# main-board.net
KiCad netlist of a schematic drawn in EAGLE
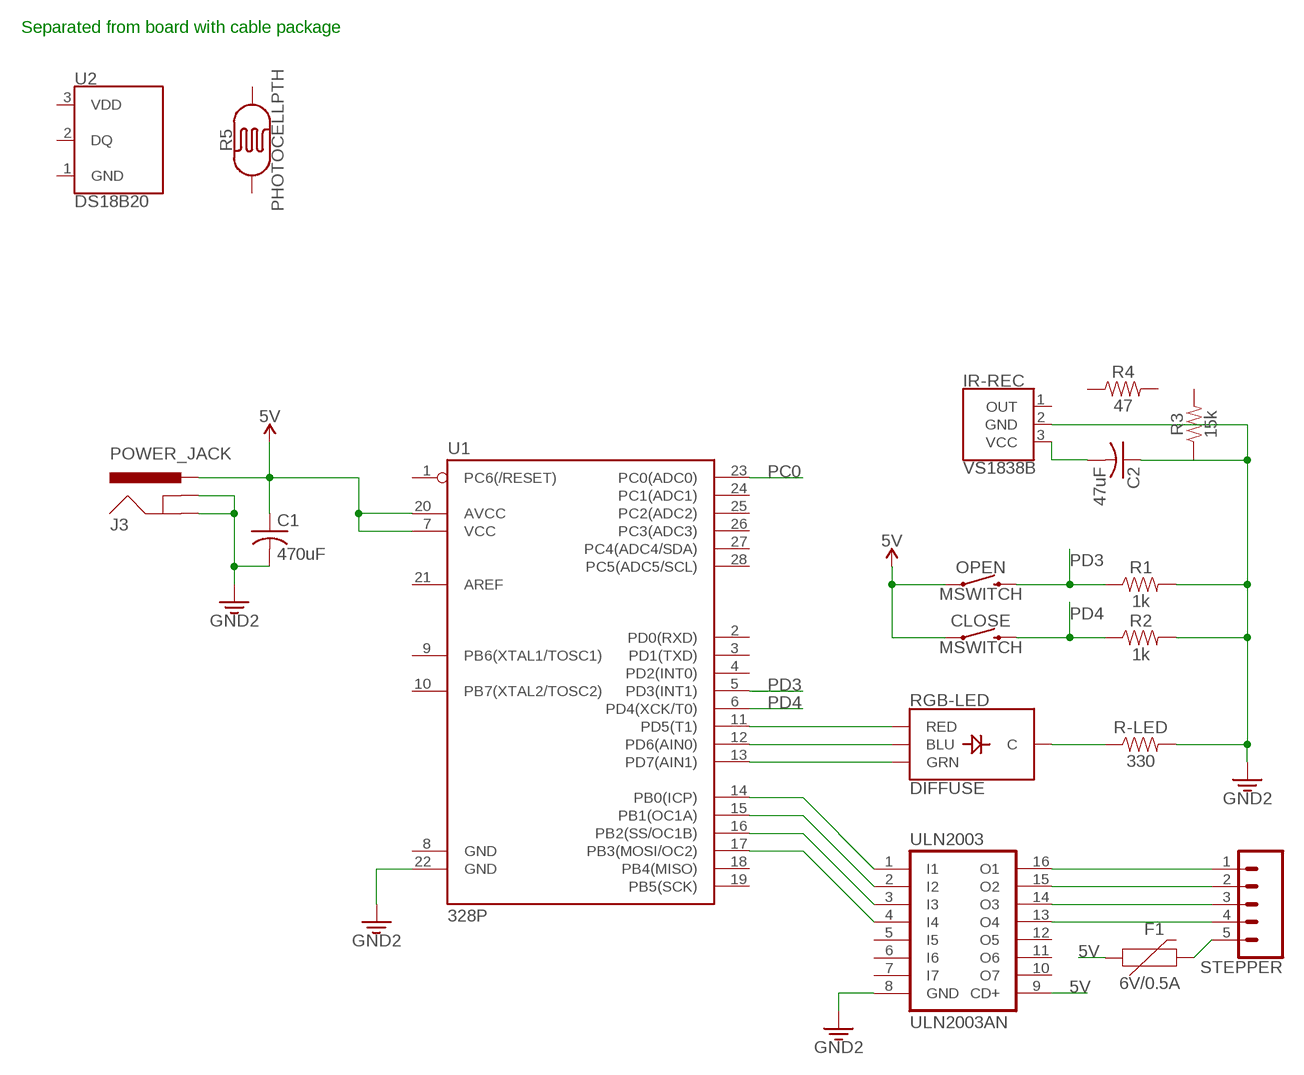
[diagram p0: schematic, sheet 1]

(export (version "E")
  (design (tool "Eeschema 10.0.6"))
  (components
    (comp (ref "C1")
      (value "470uF")
      (footprint "eagle-import:C025-050X050")
      (libsource (lib "eagle-import") (part "C-US025-050X050"))
    )
    (comp (ref "C2")
      (value "47uF")
      (footprint "eagle-import:C025-050X050")
      (libsource (lib "eagle-import") (part "C-US025-050X050"))
    )
    (comp (ref "CLOSE")
      (value "MSWITCH")
      (footprint "eagle-import:TACTILE_SWITCH_PTH_6.0MM")
      (libsource (lib "eagle-import") (part "MOMENTARY-SWITCH-SPST-PTH-6.0MM"))
    )
    (comp (ref "F1")
      (value "6V/0.5A")
      (footprint "eagle-import:1206")
      (fields (field (name "SPICEPREFIX") "F"))
      (libsource (lib "eagle-import") (part "PPTC_HALF-AMP"))
    )
    (comp (ref "IR-REC")
      (value "VS1838B")
      (footprint "eagle-import:BRM-2508_VERT")
      (libsource (lib "eagle-import") (part "BRM-2A18VERT"))
    )
    (comp (ref "J3")
      (value "POWER_JACK")
      (footprint "eagle-import:POWER_JACK_PTH")
      (libsource (lib "eagle-import") (part "POWER_JACK"))
    )
    (comp (ref "OPEN")
      (value "MSWITCH")
      (footprint "eagle-import:TACTILE_SWITCH_PTH_6.0MM")
      (libsource (lib "eagle-import") (part "MOMENTARY-SWITCH-SPST-PTH-6.0MM"))
    )
    (comp (ref "R-LED")
      (value "330")
      (footprint "eagle-import:AXIAL-0.3")
      (libsource (lib "eagle-import") (part "RESISTORAXIAL-0.3"))
    )
    (comp (ref "R1")
      (value "1k")
      (footprint "eagle-import:AXIAL-0.3")
      (libsource (lib "eagle-import") (part "1KOHM-HORIZ-1/4W-1%"))
    )
    (comp (ref "R2")
      (value "1k")
      (footprint "eagle-import:AXIAL-0.3")
      (libsource (lib "eagle-import") (part "1KOHM-HORIZ-1/4W-1%"))
    )
    (comp (ref "R3")
      (value "15k")
      (footprint "eagle-import:AXIAL-0.3")
      (libsource (lib "eagle-import") (part "RESISTORAXIAL-0.3"))
    )
    (comp (ref "R4")
      (value "47")
      (footprint "eagle-import:AXIAL-0.3")
      (libsource (lib "eagle-import") (part "RESISTORAXIAL-0.3"))
    )
    (comp (ref "R5")
      (value "PHOTOCELLPTH")
      (footprint "eagle-import:PHOTOCELL")
      (libsource (lib "eagle-import") (part "PHOTOCELLPTH"))
    )
    (comp (ref "RGB-LED")
      (value "DIFFUSE")
      (footprint "eagle-import:LED-RGB-THRU")
      (libsource (lib "eagle-import") (part "LED-RGB-CCDIFFUSE"))
    )
    (comp (ref "STEPPER")
      (value "CONN_05JST-VERT")
      (footprint "eagle-import:JST-5-PTH-VERT")
      (libsource (lib "eagle-import") (part "CONN_05JST-VERT"))
    )
    (comp (ref "U1")
      (value "328P")
      (footprint "eagle-import:DIP28")
      (libsource (lib "eagle-import") (part "ATMEGA328P_PDIP"))
    )
    (comp (ref "U2")
      (value "DS18B20")
      (footprint "eagle-import:TO-92-AMMO")
      (libsource (lib "eagle-import") (part "DS18B20"))
    )
    (comp (ref "ULN2003")
      (value "ULN2003AN")
      (footprint "eagle-import:DIL16")
      (libsource (lib "eagle-import") (part "ULN2003AN"))
    )
  )
  (nets
    (net (code "1") (name "/GND") (class "Default")
      (node (ref "U2") (pin "1") (pinfunction "GND_1") (pintype "power_in"))
    )
    (net (code "2") (name "/PC0") (class "Default")
      (node (ref "U1") (pin "23") (pinfunction "PC0(ADC0)_23") (pintype "bidirectional"))
    )
    (net (code "3") (name "/PD3") (class "Default")
      (node (ref "OPEN") (pin "3") (pinfunction "2_3") (pintype "passive"))
      (node (ref "R1") (pin "P$1") (pinfunction "1_P$1") (pintype "passive"))
      (node (ref "U1") (pin "5") (pinfunction "PD3(INT1)_5") (pintype "bidirectional"))
    )
    (net (code "4") (name "/PD4") (class "Default")
      (node (ref "CLOSE") (pin "3") (pinfunction "2_3") (pintype "passive"))
      (node (ref "R2") (pin "P$1") (pinfunction "1_P$1") (pintype "passive"))
      (node (ref "U1") (pin "6") (pinfunction "PD4(XCK/T0)_6") (pintype "bidirectional"))
    )
    (net (code "5") (name "/VDD") (class "Default")
      (node (ref "U2") (pin "3") (pinfunction "VDD_3") (pintype "power_in"))
    )
    (net (code "6") (name "5V") (class "Default")
      (node (ref "C1") (pin "1") (pinfunction "1_1") (pintype "passive"))
      (node (ref "CLOSE") (pin "1") (pinfunction "1_1") (pintype "passive"))
      (node (ref "F1") (pin "1") (pinfunction "1_1") (pintype "bidirectional"))
      (node (ref "J3") (pin "PWR") (pinfunction "PWR_PWR") (pintype "bidirectional"))
      (node (ref "OPEN") (pin "1") (pinfunction "1_1") (pintype "passive"))
      (node (ref "U1") (pin "20") (pinfunction "AVCC_20") (pintype "bidirectional"))
      (node (ref "U1") (pin "7") (pinfunction "VCC_7") (pintype "bidirectional"))
      (node (ref "ULN2003") (pin "9") (pinfunction "CD+_9") (pintype "passive"))
    )
    (net (code "7") (name "GND2") (class "Default")
      (node (ref "C1") (pin "2") (pinfunction "2_2") (pintype "passive"))
      (node (ref "C2") (pin "1") (pinfunction "1_1") (pintype "passive"))
      (node (ref "IR-REC") (pin "2") (pinfunction "GND_2") (pintype "bidirectional"))
      (node (ref "J3") (pin "GND") (pinfunction "GND_GND") (pintype "bidirectional"))
      (node (ref "J3") (pin "GNDBREAK") (pinfunction "GNDBREAK_GNDBREAK") (pintype "bidirectional"))
      (node (ref "R-LED") (pin "P$2") (pinfunction "2_P$2") (pintype "passive"))
      (node (ref "R1") (pin "P$2") (pinfunction "2_P$2") (pintype "passive"))
      (node (ref "R2") (pin "P$2") (pinfunction "2_P$2") (pintype "passive"))
      (node (ref "U1") (pin "22") (pinfunction "GND_22") (pintype "bidirectional"))
      (node (ref "ULN2003") (pin "8") (pinfunction "GND_8") (pintype "power_in"))
    )
    (net (code "8") (name "Net-(F1-Pad2)") (class "Default")
      (node (ref "F1") (pin "2") (pinfunction "2_2") (pintype "bidirectional"))
      (node (ref "STEPPER") (pin "5") (pinfunction "5_5") (pintype "passive"))
    )
    (net (code "9") (name "Net-(IR-REC-VCC)") (class "Default")
      (node (ref "C2") (pin "2") (pinfunction "2_2") (pintype "passive"))
      (node (ref "IR-REC") (pin "3") (pinfunction "VCC_3") (pintype "bidirectional"))
    )
    (net (code "10") (name "Net-(R-LED-1)") (class "Default")
      (node (ref "R-LED") (pin "P$1") (pinfunction "1_P$1") (pintype "passive"))
      (node (ref "RGB-LED") (pin "2") (pinfunction "C_2") (pintype "bidirectional"))
    )
    (net (code "11") (name "Net-(RGB-LED-BLU)") (class "Default")
      (node (ref "RGB-LED") (pin "4") (pinfunction "BLU_4") (pintype "bidirectional"))
      (node (ref "U1") (pin "12") (pinfunction "PD6(AIN0)_12") (pintype "bidirectional"))
    )
    (net (code "12") (name "Net-(RGB-LED-GRN)") (class "Default")
      (node (ref "RGB-LED") (pin "3") (pinfunction "GRN_3") (pintype "bidirectional"))
      (node (ref "U1") (pin "13") (pinfunction "PD7(AIN1)_13") (pintype "bidirectional"))
    )
    (net (code "13") (name "Net-(RGB-LED-RED)") (class "Default")
      (node (ref "RGB-LED") (pin "1") (pinfunction "RED_1") (pintype "bidirectional"))
      (node (ref "U1") (pin "11") (pinfunction "PD5(T1)_11") (pintype "bidirectional"))
    )
    (net (code "14") (name "Net-(U1-PB0(ICP))") (class "Default")
      (node (ref "U1") (pin "14") (pinfunction "PB0(ICP)_14") (pintype "bidirectional"))
      (node (ref "ULN2003") (pin "1") (pinfunction "I1_1") (pintype "input"))
    )
    (net (code "15") (name "Net-(U1-PB1(OC1A))") (class "Default")
      (node (ref "U1") (pin "15") (pinfunction "PB1(OC1A)_15") (pintype "bidirectional"))
      (node (ref "ULN2003") (pin "2") (pinfunction "I2_2") (pintype "input"))
    )
    (net (code "16") (name "Net-(U1-PB2(SS{slash}OC1B))") (class "Default")
      (node (ref "U1") (pin "16") (pinfunction "PB2(SS/OC1B)_16") (pintype "bidirectional"))
      (node (ref "ULN2003") (pin "3") (pinfunction "I3_3") (pintype "input"))
    )
    (net (code "17") (name "Net-(U1-PB3(MOSI{slash}OC2))") (class "Default")
      (node (ref "U1") (pin "17") (pinfunction "PB3(MOSI/OC2)_17") (pintype "bidirectional"))
      (node (ref "ULN2003") (pin "4") (pinfunction "I4_4") (pintype "input"))
    )
    (net (code "18") (name "Net-(ULN2003-O1)") (class "Default")
      (node (ref "STEPPER") (pin "1") (pinfunction "1_1") (pintype "passive"))
      (node (ref "ULN2003") (pin "16") (pinfunction "O1_16") (pintype "open_collector"))
    )
    (net (code "19") (name "Net-(ULN2003-O2)") (class "Default")
      (node (ref "STEPPER") (pin "2") (pinfunction "2_2") (pintype "passive"))
      (node (ref "ULN2003") (pin "15") (pinfunction "O2_15") (pintype "open_collector"))
    )
    (net (code "20") (name "Net-(ULN2003-O3)") (class "Default")
      (node (ref "STEPPER") (pin "3") (pinfunction "3_3") (pintype "passive"))
      (node (ref "ULN2003") (pin "14") (pinfunction "O3_14") (pintype "open_collector"))
    )
    (net (code "21") (name "Net-(ULN2003-O4)") (class "Default")
      (node (ref "STEPPER") (pin "4") (pinfunction "4_4") (pintype "passive"))
      (node (ref "ULN2003") (pin "13") (pinfunction "O4_13") (pintype "open_collector"))
    )
    (net (code "22") (name "unconnected-(IR-REC-OUT-Pad1)") (class "Default")
      (node (ref "IR-REC") (pin "1") (pinfunction "OUT_1") (pintype "bidirectional"))
    )
    (net (code "23") (name "unconnected-(R3-1-PadP$1)") (class "Default")
      (node (ref "R3") (pin "P$1") (pinfunction "1_P$1") (pintype "passive"))
    )
    (net (code "24") (name "unconnected-(R3-2-PadP$2)") (class "Default")
      (node (ref "R3") (pin "P$2") (pinfunction "2_P$2") (pintype "passive"))
    )
    (net (code "25") (name "unconnected-(R4-1-PadP$1)") (class "Default")
      (node (ref "R4") (pin "P$1") (pinfunction "1_P$1") (pintype "passive"))
    )
    (net (code "26") (name "unconnected-(R4-2-PadP$2)") (class "Default")
      (node (ref "R4") (pin "P$2") (pinfunction "2_P$2") (pintype "passive"))
    )
    (net (code "27") (name "unconnected-(R5-P$1-Pad1)") (class "Default")
      (node (ref "R5") (pin "1") (pinfunction "P$1_1") (pintype "bidirectional"))
    )
    (net (code "28") (name "unconnected-(R5-P$2-Pad2)") (class "Default")
      (node (ref "R5") (pin "2") (pinfunction "P$2_2") (pintype "bidirectional"))
    )
    (net (code "29") (name "unconnected-(U1-AREF-Pad21)") (class "Default")
      (node (ref "U1") (pin "21") (pinfunction "AREF_21") (pintype "bidirectional"))
    )
    (net (code "30") (name "unconnected-(U1-GND-Pad8)") (class "Default")
      (node (ref "U1") (pin "8") (pinfunction "GND_8") (pintype "bidirectional"))
    )
    (net (code "31") (name "unconnected-(U1-PB4(MISO)-Pad18)") (class "Default")
      (node (ref "U1") (pin "18") (pinfunction "PB4(MISO)_18") (pintype "bidirectional"))
    )
    (net (code "32") (name "unconnected-(U1-PB5(SCK)-Pad19)") (class "Default")
      (node (ref "U1") (pin "19") (pinfunction "PB5(SCK)_19") (pintype "bidirectional"))
    )
    (net (code "33") (name "unconnected-(U1-PB6(XTAL1{slash}TOSC1)-Pad9)") (class "Default")
      (node (ref "U1") (pin "9") (pinfunction "PB6(XTAL1/TOSC1)_9") (pintype "bidirectional"))
    )
    (net (code "34") (name "unconnected-(U1-PB7(XTAL2{slash}TOSC2)-Pad10)") (class "Default")
      (node (ref "U1") (pin "10") (pinfunction "PB7(XTAL2/TOSC2)_10") (pintype "bidirectional"))
    )
    (net (code "35") (name "unconnected-(U1-PC1(ADC1)-Pad24)") (class "Default")
      (node (ref "U1") (pin "24") (pinfunction "PC1(ADC1)_24") (pintype "bidirectional"))
    )
    (net (code "36") (name "unconnected-(U1-PC2(ADC2)-Pad25)") (class "Default")
      (node (ref "U1") (pin "25") (pinfunction "PC2(ADC2)_25") (pintype "bidirectional"))
    )
    (net (code "37") (name "unconnected-(U1-PC3(ADC3)-Pad26)") (class "Default")
      (node (ref "U1") (pin "26") (pinfunction "PC3(ADC3)_26") (pintype "bidirectional"))
    )
    (net (code "38") (name "unconnected-(U1-PC4(ADC4{slash}SDA)-Pad27)") (class "Default")
      (node (ref "U1") (pin "27") (pinfunction "PC4(ADC4/SDA)_27") (pintype "bidirectional"))
    )
    (net (code "39") (name "unconnected-(U1-PC5(ADC5{slash}SCL)-Pad28)") (class "Default")
      (node (ref "U1") (pin "28") (pinfunction "PC5(ADC5/SCL)_28") (pintype "bidirectional"))
    )
    (net (code "40") (name "unconnected-(U1-PC6({slash}RESET)-Pad1)") (class "Default")
      (node (ref "U1") (pin "1") (pinfunction "PC6(/RESET)_1") (pintype "bidirectional"))
    )
    (net (code "41") (name "unconnected-(U1-PD0(RXD)-Pad2)") (class "Default")
      (node (ref "U1") (pin "2") (pinfunction "PD0(RXD)_2") (pintype "bidirectional"))
    )
    (net (code "42") (name "unconnected-(U1-PD1(TXD)-Pad3)") (class "Default")
      (node (ref "U1") (pin "3") (pinfunction "PD1(TXD)_3") (pintype "bidirectional"))
    )
    (net (code "43") (name "unconnected-(U1-PD2(INT0)-Pad4)") (class "Default")
      (node (ref "U1") (pin "4") (pinfunction "PD2(INT0)_4") (pintype "bidirectional"))
    )
    (net (code "44") (name "unconnected-(U2-DQ-Pad2)") (class "Default")
      (node (ref "U2") (pin "2") (pinfunction "DQ_2") (pintype "bidirectional"))
    )
    (net (code "45") (name "unconnected-(ULN2003-I5-Pad5)") (class "Default")
      (node (ref "ULN2003") (pin "5") (pinfunction "I5_5") (pintype "input"))
    )
    (net (code "46") (name "unconnected-(ULN2003-I6-Pad6)") (class "Default")
      (node (ref "ULN2003") (pin "6") (pinfunction "I6_6") (pintype "input"))
    )
    (net (code "47") (name "unconnected-(ULN2003-I7-Pad7)") (class "Default")
      (node (ref "ULN2003") (pin "7") (pinfunction "I7_7") (pintype "input"))
    )
    (net (code "48") (name "unconnected-(ULN2003-O5-Pad12)") (class "Default")
      (node (ref "ULN2003") (pin "12") (pinfunction "O5_12") (pintype "open_collector"))
    )
    (net (code "49") (name "unconnected-(ULN2003-O6-Pad11)") (class "Default")
      (node (ref "ULN2003") (pin "11") (pinfunction "O6_11") (pintype "open_collector"))
    )
    (net (code "50") (name "unconnected-(ULN2003-O7-Pad10)") (class "Default")
      (node (ref "ULN2003") (pin "10") (pinfunction "O7_10") (pintype "open_collector"))
    )
  )
)
